# LED-drive-Green.net
KiCad netlist of a schematic drawn in Altium Designer
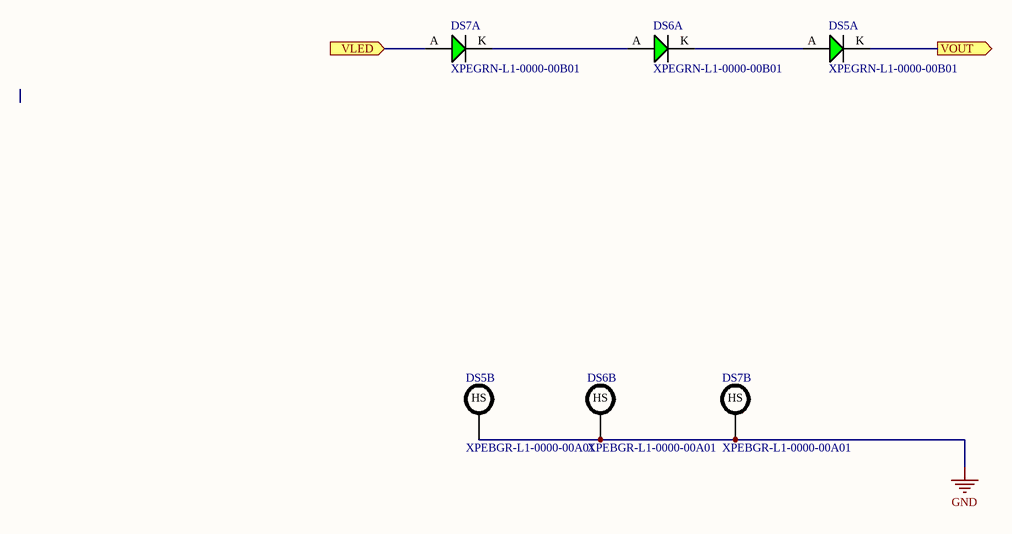
[diagram p0: LED-drive-Green.SchDoc]

(export (version "E")
  (design (tool "Eeschema 10.0.6"))
  (components
    (comp (ref "DS5")
      (value "XPEGRN-L1-0000-00B01")
      (footprint "Cree XLamp XP-E2 (red and green LED)")
      (description "LED, Cree XLamp XP-E2 Series, Green, 535 nm, 135 °, 87.4 lm, 1 A")
      (libsource (lib "TSAL") (part "XPEBGR-L1-0000-00A01"))
    )
    (comp (ref "DS6")
      (value "XPEGRN-L1-0000-00B01")
      (footprint "Cree XLamp XP-E2 (red and green LED)")
      (description "LED, Cree XLamp XP-E2 Series, Green, 535 nm, 135 °, 87.4 lm, 1 A")
      (libsource (lib "TSAL") (part "XPEBGR-L1-0000-00A01"))
    )
    (comp (ref "DS7")
      (value "XPEGRN-L1-0000-00B01")
      (footprint "Cree XLamp XP-E2 (red and green LED)")
      (description "LED, Cree XLamp XP-E2 Series, Green, 535 nm, 135 °, 87.4 lm, 1 A")
      (libsource (lib "TSAL") (part "XPEBGR-L1-0000-00A01"))
    )
  )
  (nets
    (net (code "1") (name "/VLED") (class "Default")
      (node (ref "DS7") (pin "A") (pinfunction "A_A") (pintype "passive"))
    )
    (net (code "2") (name "/VOUT") (class "Default")
      (node (ref "DS5") (pin "K") (pinfunction "K_K") (pintype "passive"))
    )
    (net (code "3") (name "GND") (class "Default")
      (node (ref "DS5") (pin "HS") (pinfunction "HS_HS") (pintype "passive"))
      (node (ref "DS6") (pin "HS") (pinfunction "HS_HS") (pintype "passive"))
      (node (ref "DS7") (pin "HS") (pinfunction "HS_HS") (pintype "passive"))
    )
    (net (code "4") (name "Net-(DS5-PadA)") (class "Default")
      (node (ref "DS5") (pin "A") (pinfunction "A_A") (pintype "passive"))
      (node (ref "DS6") (pin "K") (pinfunction "K_K") (pintype "passive"))
    )
    (net (code "5") (name "Net-(DS6-PadA)") (class "Default")
      (node (ref "DS6") (pin "A") (pinfunction "A_A") (pintype "passive"))
      (node (ref "DS7") (pin "K") (pinfunction "K_K") (pintype "passive"))
    )
  )
)
